# ALLPRINT-CAPBOARD-677512-POWER.net
KiCad netlist of a schematic drawn in Altium Designer
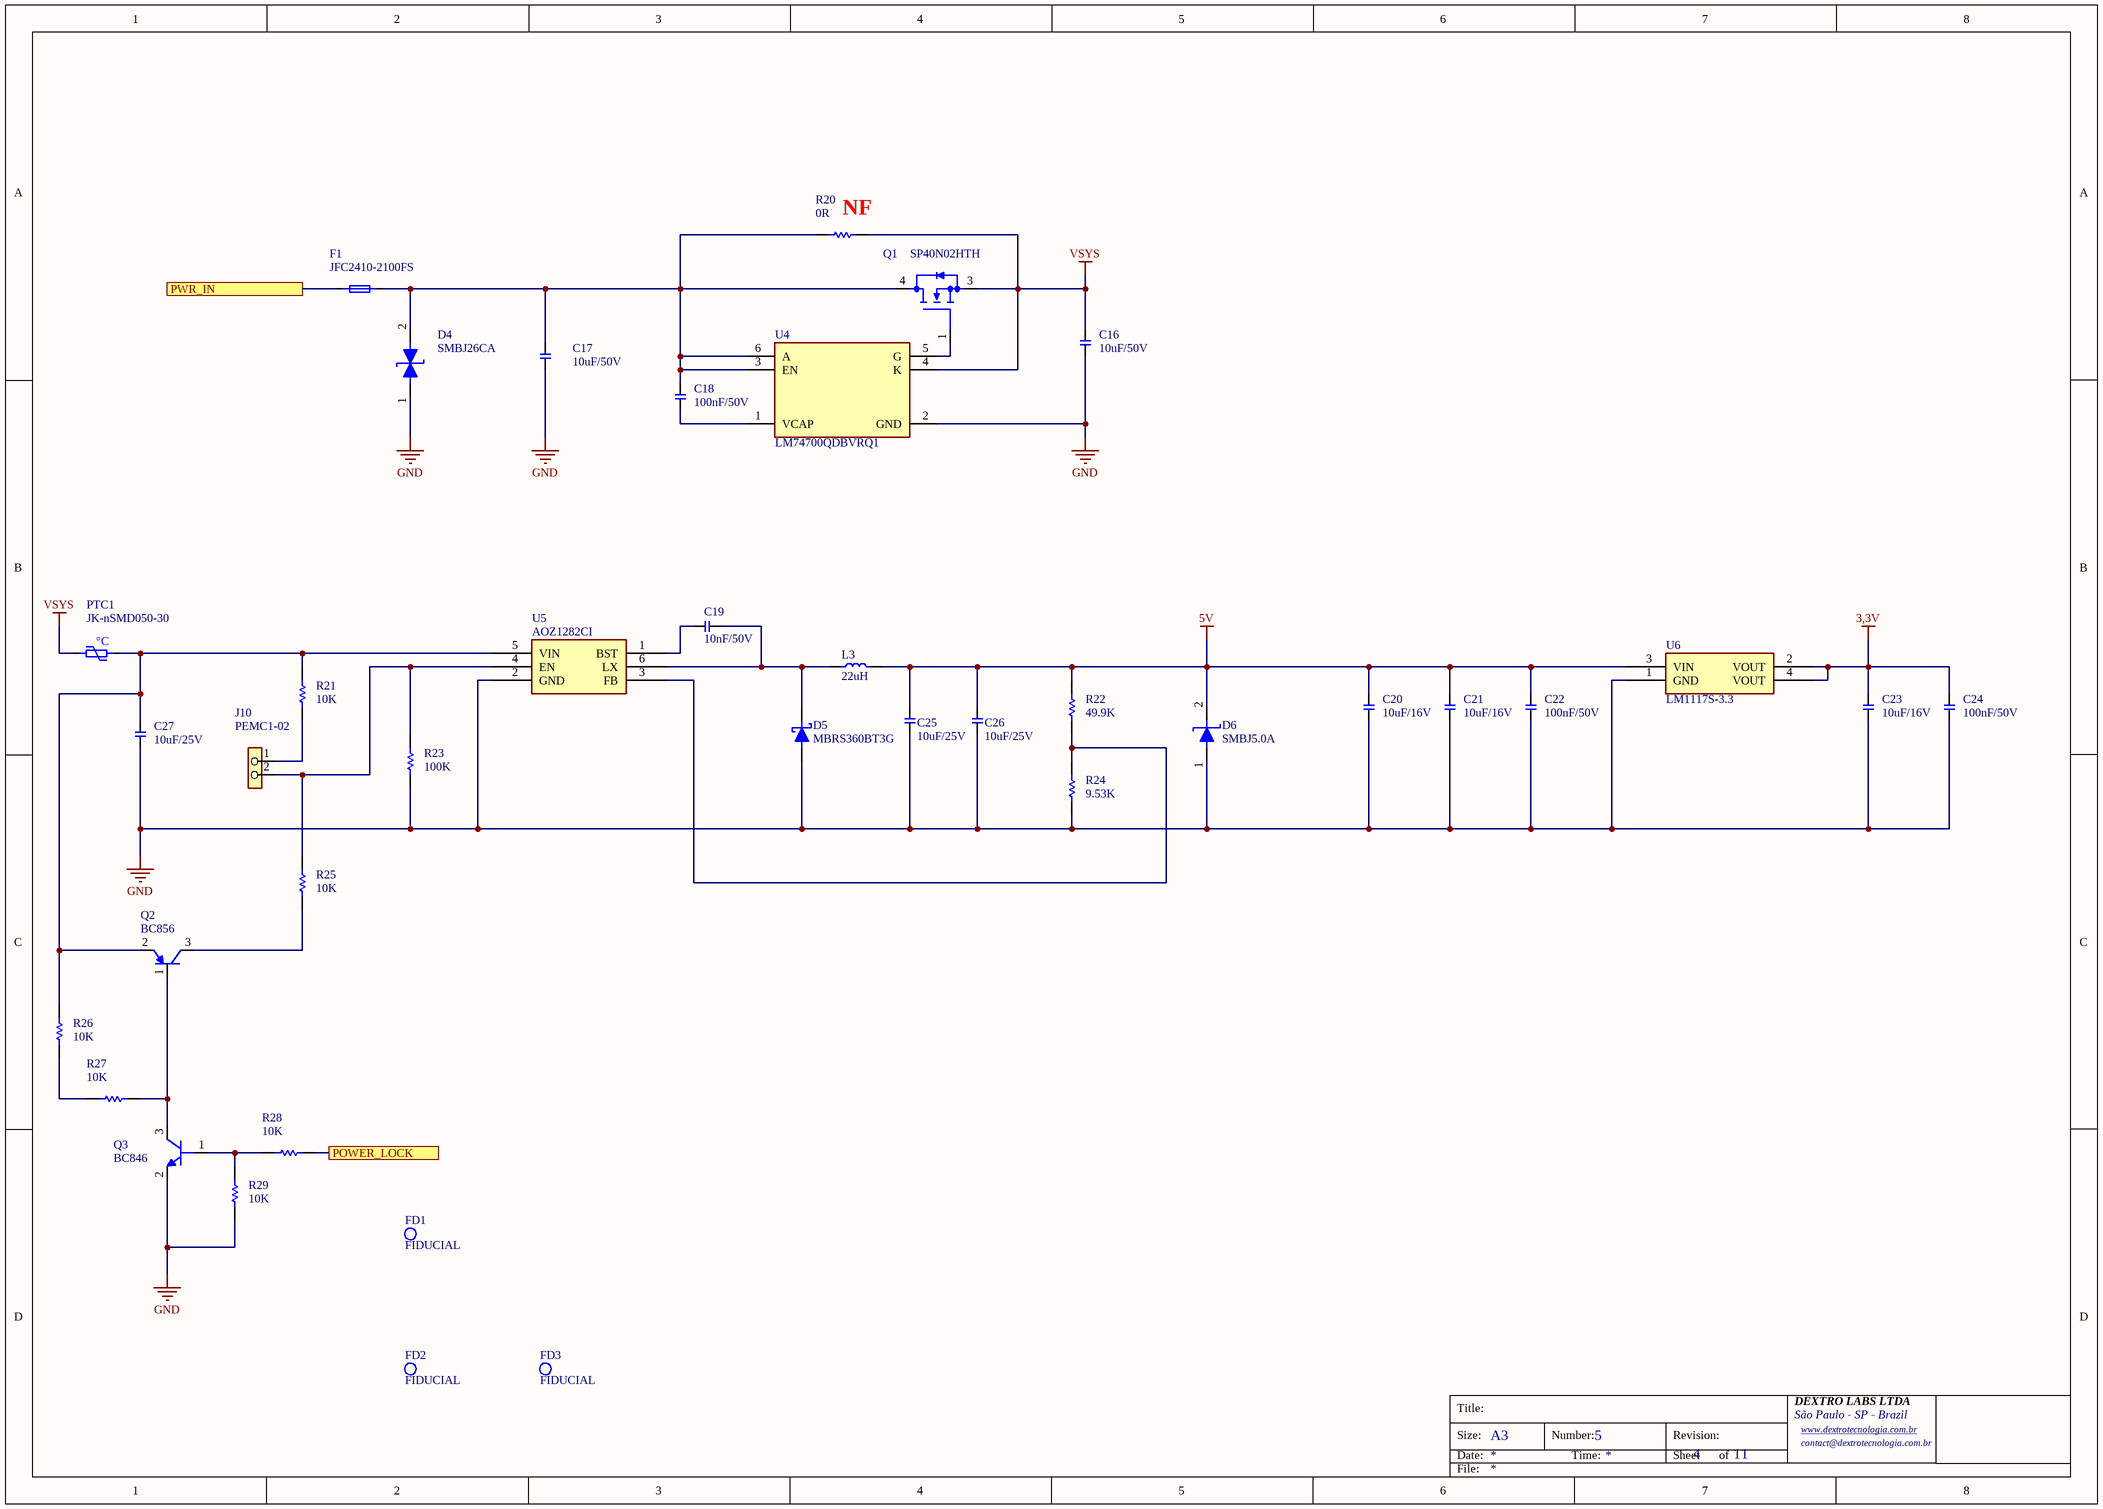
[diagram p0: ALLPRINT-CAPBOARD-677512-POWER.SchDoc]

(export (version "E")
  (design (tool "Eeschema 10.0.6"))
  (components
    (comp (ref "C16")
      (value "10uF/50V")
      (footprint "CAP-0805")
      (description "50V 10uF X5R ±10% 1206 Multilayer Ceramic Capacitors MLCC - SMD/SMT ROHS")
      (libsource (lib "dextro-labs") (part "CAP-10uF/50V-0805-X5R-MLCC"))
    )
    (comp (ref "C17")
      (value "10uF/50V")
      (footprint "CAP-0805")
      (description "50V 10uF X5R ±10% 1206 Multilayer Ceramic Capacitors MLCC - SMD/SMT ROHS")
      (libsource (lib "dextro-labs") (part "CAP-10uF/50V-0805-X5R-MLCC"))
    )
    (comp (ref "C18")
      (value "100nF/50V")
      (footprint "CAP-0603")
      (description "50V 100nF X7R ±10% 0603 Multilayer Ceramic Capacitors MLCC - SMD/SMT ROHS")
      (libsource (lib "dextro-labs") (part "CAP-100nF/50V-0603-X7R-MLCC"))
    )
    (comp (ref "C19")
      (value "10nF/50V")
      (footprint "CAP-0603")
      (description "50V 10nF X7R ±10% 0603 Multilayer Ceramic Capacitors MLCC - SMD/SMT ROHS")
      (libsource (lib "dextro-labs") (part "CAP-10nF/50V-0603-X7R-MLCC"))
    )
    (comp (ref "C20")
      (value "10uF/16V")
      (footprint "CAP-0603")
      (description "16V 10uF X5R ±20% 0603 Multilayer Ceramic Capacitors MLCC - SMD/SMT ROHS")
      (libsource (lib "dextro-labs") (part "CAP-10uF/16V-0603-X5R"))
    )
    (comp (ref "C21")
      (value "10uF/16V")
      (footprint "CAP-0603")
      (description "16V 10uF X5R ±20% 0603 Multilayer Ceramic Capacitors MLCC - SMD/SMT ROHS")
      (libsource (lib "dextro-labs") (part "CAP-10uF/16V-0603-X5R"))
    )
    (comp (ref "C22")
      (value "100nF/50V")
      (footprint "CAP-0603")
      (description "50V 100nF X7R ±10% 0603 Multilayer Ceramic Capacitors MLCC - SMD/SMT ROHS")
      (libsource (lib "dextro-labs") (part "CAP-100nF/50V-0603-X7R-MLCC"))
    )
    (comp (ref "C23")
      (value "10uF/16V")
      (footprint "CAP-0603")
      (description "16V 10uF X5R ±20% 0603 Multilayer Ceramic Capacitors MLCC - SMD/SMT ROHS")
      (libsource (lib "dextro-labs") (part "CAP-10uF/16V-0603-X5R"))
    )
    (comp (ref "C24")
      (value "100nF/50V")
      (footprint "CAP-0603")
      (description "50V 100nF X7R ±10% 0603 Multilayer Ceramic Capacitors MLCC - SMD/SMT ROHS")
      (libsource (lib "dextro-labs") (part "CAP-100nF/50V-0603-X7R-MLCC"))
    )
    (comp (ref "C25")
      (value "10uF/25V")
      (footprint "CAP-0805")
      (description "25V 10uF X5R ±10% 0805 Ceramic Capacitors ROHS")
      (libsource (lib "dextro-labs") (part "CAP-10uF/25V-0805-X5R-MLCC"))
    )
    (comp (ref "C26")
      (value "10uF/25V")
      (footprint "CAP-0805")
      (description "25V 10uF X5R ±10% 0805 Ceramic Capacitors ROHS")
      (libsource (lib "dextro-labs") (part "CAP-10uF/25V-0805-X5R-MLCC"))
    )
    (comp (ref "C27")
      (value "10uF/25V")
      (footprint "CAP-0805")
      (description "25V 10uF X5R ±10% 0805 Ceramic Capacitors ROHS")
      (libsource (lib "dextro-labs") (part "CAP-10uF/25V-0805-X5R-MLCC"))
    )
    (comp (ref "D4")
      (value "SMBJ26CA")
      (footprint "DO214-AA")
      (description "28.9V 26V 42.1V 14.2A 600W Bidirectional DO-214AA(SMB) TVS Diodes RoHS")
      (libsource (lib "dextro-labs") (part "SMBJ26CA"))
    )
    (comp (ref "D5")
      (value "MBRS360BT3G")
      (footprint "DO214-AA")
      (description "125A 60V 630mV@3A 3A SMB(DO-214AA) Single Diodes RoHS")
      (libsource (lib "dextro-labs") (part "DIODE-SCHOTTKY-60V-3A-MBRS360BT3G"))
    )
    (comp (ref "D6")
      (value "SMBJ5.0A")
      (footprint "DO214-AA")
      (description "65.3A 600W 9.2V 6.4V Unidirectional 5V DO-214AA TVS Diodes RoHS")
      (libsource (lib "dextro-labs") (part "SMBJ5.0A"))
    )
    (comp (ref "F1")
      (value "JFC2410-2100FS")
      (footprint "FUSE-2410")
      (description "125V Surface Mount Fuse 10A 2410 Fuses RoHS")
      (libsource (lib "dextro-labs") (part "FUSE-125V-10A-2410"))
    )
    (comp (ref "FD1")
      (value "FIDUCIAL")
      (footprint "FIDUCIAL")
      (libsource (lib "dextro-labs") (part "FIDUCIAL"))
    )
    (comp (ref "FD2")
      (value "FIDUCIAL")
      (footprint "FIDUCIAL")
      (libsource (lib "dextro-labs") (part "FIDUCIAL"))
    )
    (comp (ref "FD3")
      (value "FIDUCIAL")
      (footprint "FIDUCIAL")
      (libsource (lib "dextro-labs") (part "FIDUCIAL"))
    )
    (comp (ref "J10")
      (value "PEMC1-02")
      (footprint "PEMC1-02")
      (description "CONECTOR PASSO 2,5mm\r\n250VCA\r\n3A\r\n10mOHMS")
      (libsource (lib "dextro-labs") (part "PEMC1-02"))
    )
    (comp (ref "L3")
      (value "22uH")
      (footprint "INDUTOR-6672")
      (description "2.6A 22uH ±20% 110mΩ SMD,7.2x6.6mm Fixed Inductors RoHS")
      (libsource (lib "dextro-labs") (part "FIXED-INDUCTOR-SMD-22uH-7.2X6.6mm-2.6A-110mΩ"))
    )
    (comp (ref "PTC1")
      (value "JK-nSMD050-30")
      (footprint "PTC-1206")
      (description "30V 500mA 100A 1A 150mΩ 1206 PTC Resettable Fuses ROHS")
      (libsource (lib "dextro-labs") (part "PTC-FUSE-30V-500mA-1206"))
    )
    (comp (ref "Q1")
      (value "SP40N02HTH")
      (footprint "TO-252-2")
      (description "40V 130A 2.5mΩ@10V 125W TO-252 Single FETs, MOSFETs RoHS")
      (libsource (lib "dextro-labs") (part "TRAN-MOSFET-N-CHAN-40V-130A-DPAK"))
    )
    (comp (ref "Q2")
      (value "BC856")
      (footprint "SOT23-3")
      (description "65V 220@2mA,5V 250mW 100mA PNP SOT-23 Bipolar (BJT) ROHS")
      (libsource (lib "dextro-labs") (part "TRANSISTOR-BC856B,215"))
    )
    (comp (ref "Q3")
      (value "BC846")
      (footprint "SOT23-3")
      (description "65V 200@10mA,5V 250mW 100mA NPN SOT-23 Bipolar (BJT) ROHS")
      (libsource (lib "dextro-labs") (part "TRANSISTOR-BC846B,215-SOT23"))
    )
    (comp (ref "R20")
      (value "0R")
      (footprint "RES-1206")
      (description "0Ω 250mW 200V Thick Film Resistor ±1% 1206 Chip Resistor - Surface Mount RoHS")
      (libsource (lib "dextro-labs") (part "RES-0R-1%-250mW-1206"))
    )
    (comp (ref "R21")
      (value "10K")
      (footprint "RES-0603")
      (description "100mW Thick Film Resistor 75V ±100ppm/℃ ±1% 10kΩ 0603 Chip Resistor - Surface Mount ROHS")
      (libsource (lib "dextro-labs") (part "RES-10K-1%-100mW-0603"))
    )
    (comp (ref "R22")
      (value "49.9K")
      (footprint "RES-0603")
      (description "100mW 49.9kΩ 75V ±100ppm/℃ Thick Film Resistor ±1% 0603 Chip Resistor - Surface Mount ROHS")
      (libsource (lib "dextro-labs") (part "RES-49.9K-1%-100mW-0603"))
    )
    (comp (ref "R23")
      (value "100K")
      (footprint "RES-0603")
      (description "100mW Thick Film Resistor 75V ±100ppm/℃ ±1% 100kΩ 0603 Chip Resistor - Surface Mount ROHS")
      (libsource (lib "dextro-labs") (part "RES-100K-1%-100mW-0603"))
    )
    (comp (ref "R24")
      (value "9.53K")
      (footprint "RES-0603")
      (description "100mW 9.53kΩ 75V ±100ppm/℃ Thick Film Resistor ±1% 0603 Chip Resistor - Surface Mount ROHS")
      (libsource (lib "dextro-labs") (part "RES-9.53K-1%-100mW-0603"))
    )
    (comp (ref "R25")
      (value "10K")
      (footprint "RES-0603")
      (description "100mW Thick Film Resistor 75V ±100ppm/℃ ±1% 10kΩ 0603 Chip Resistor - Surface Mount ROHS")
      (libsource (lib "dextro-labs") (part "RES-10K-1%-100mW-0603"))
    )
    (comp (ref "R26")
      (value "10K")
      (footprint "RES-0603")
      (description "100mW Thick Film Resistor 75V ±100ppm/℃ ±1% 10kΩ 0603 Chip Resistor - Surface Mount ROHS")
      (libsource (lib "dextro-labs") (part "RES-10K-1%-100mW-0603"))
    )
    (comp (ref "R27")
      (value "10K")
      (footprint "RES-0603")
      (description "100mW Thick Film Resistor 75V ±100ppm/℃ ±1% 10kΩ 0603 Chip Resistor - Surface Mount ROHS")
      (libsource (lib "dextro-labs") (part "RES-10K-1%-100mW-0603"))
    )
    (comp (ref "R28")
      (value "10K")
      (footprint "RES-0603")
      (description "100mW Thick Film Resistor 75V ±100ppm/℃ ±1% 10kΩ 0603 Chip Resistor - Surface Mount ROHS")
      (libsource (lib "dextro-labs") (part "RES-10K-1%-100mW-0603"))
    )
    (comp (ref "R29")
      (value "10K")
      (footprint "RES-0603")
      (description "100mW Thick Film Resistor 75V ±100ppm/℃ ±1% 10kΩ 0603 Chip Resistor - Surface Mount ROHS")
      (libsource (lib "dextro-labs") (part "RES-10K-1%-100mW-0603"))
    )
    (comp (ref "U4")
      (value "LM74700QDBVRQ1")
      (footprint "SOT23-6")
      (description "Low IQ Battery Reverse Protection Ideal Diode Controller")
      (libsource (lib "dextro-labs") (part "IC-OR-CONTROLLER-LM74700QDBVRQ1"))
    )
    (comp (ref "U5")
      (value "AOZ1282CI")
      (footprint "SOT23-6")
      (description "Step-down type Adjustable 800mV~36V 1.2A 4.5V~36V SOT-23-6 DC-DC Converters ROHS")
      (libsource (lib "dextro-sch") (part "AOZ1282CI"))
    )
    (comp (ref "U6")
      (value "LM1117S-3.3")
      (footprint "SOT223")
      (libsource (lib "dextro-labs") (part "LM1117S-3.3"))
    )
  )
  (nets
    (net (code "1") (name "/POWER_LOCK") (class "Default")
      (node (ref "R28") (pin "1") (pinfunction "1_1") (pintype "passive"))
    )
    (net (code "2") (name "/PWR_IN") (class "Default")
      (node (ref "F1") (pin "1") (pinfunction "1_1") (pintype "passive"))
    )
    (net (code "3") (name "3,3V") (class "Default")
      (node (ref "C23") (pin "2") (pinfunction "2_2") (pintype "passive"))
      (node (ref "C24") (pin "2") (pinfunction "2_2") (pintype "passive"))
      (node (ref "U6") (pin "2") (pinfunction "VOUT_2") (pintype "passive"))
      (node (ref "U6") (pin "4") (pinfunction "VOUT_4") (pintype "passive"))
    )
    (net (code "4") (name "5V") (class "Default")
      (node (ref "C20") (pin "2") (pinfunction "2_2") (pintype "passive"))
      (node (ref "C21") (pin "2") (pinfunction "2_2") (pintype "passive"))
      (node (ref "C22") (pin "2") (pinfunction "2_2") (pintype "passive"))
      (node (ref "C25") (pin "2") (pinfunction "2_2") (pintype "passive"))
      (node (ref "C26") (pin "2") (pinfunction "2_2") (pintype "passive"))
      (node (ref "D6") (pin "2") (pinfunction "K_2") (pintype "passive"))
      (node (ref "L3") (pin "2") (pinfunction "2_2") (pintype "passive"))
      (node (ref "R22") (pin "2") (pinfunction "2_2") (pintype "passive"))
      (node (ref "U6") (pin "3") (pinfunction "VIN_3") (pintype "passive"))
    )
    (net (code "5") (name "GND") (class "Default")
      (node (ref "C16") (pin "1") (pinfunction "1_1") (pintype "passive"))
      (node (ref "C17") (pin "1") (pinfunction "1_1") (pintype "passive"))
      (node (ref "C20") (pin "1") (pinfunction "1_1") (pintype "passive"))
      (node (ref "C21") (pin "1") (pinfunction "1_1") (pintype "passive"))
      (node (ref "C22") (pin "1") (pinfunction "1_1") (pintype "passive"))
      (node (ref "C23") (pin "1") (pinfunction "1_1") (pintype "passive"))
      (node (ref "C24") (pin "1") (pinfunction "1_1") (pintype "passive"))
      (node (ref "C25") (pin "1") (pinfunction "1_1") (pintype "passive"))
      (node (ref "C26") (pin "1") (pinfunction "1_1") (pintype "passive"))
      (node (ref "C27") (pin "1") (pinfunction "1_1") (pintype "passive"))
      (node (ref "D4") (pin "1") (pinfunction "A1_1") (pintype "passive"))
      (node (ref "D5") (pin "1") (pinfunction "A_1") (pintype "passive"))
      (node (ref "D6") (pin "1") (pinfunction "A_1") (pintype "passive"))
      (node (ref "Q3") (pin "2") (pinfunction "2_2") (pintype "passive"))
      (node (ref "R23") (pin "1") (pinfunction "1_1") (pintype "passive"))
      (node (ref "R24") (pin "1") (pinfunction "1_1") (pintype "passive"))
      (node (ref "R29") (pin "2") (pinfunction "2_2") (pintype "passive"))
      (node (ref "U4") (pin "2") (pinfunction "GND_2") (pintype "passive"))
      (node (ref "U5") (pin "2") (pinfunction "GND_2") (pintype "passive"))
      (node (ref "U6") (pin "1") (pinfunction "GND_1") (pintype "passive"))
    )
    (net (code "6") (name "Net-(D4-A2)") (class "Default")
      (node (ref "C17") (pin "2") (pinfunction "2_2") (pintype "passive"))
      (node (ref "C18") (pin "2") (pinfunction "2_2") (pintype "passive"))
      (node (ref "D4") (pin "2") (pinfunction "A2_2") (pintype "passive"))
      (node (ref "F1") (pin "2") (pinfunction "2_2") (pintype "passive"))
      (node (ref "Q1") (pin "4") (pinfunction "D_4") (pintype "passive"))
      (node (ref "R20") (pin "1") (pinfunction "1_1") (pintype "passive"))
      (node (ref "U4") (pin "3") (pinfunction "EN_3") (pintype "passive"))
      (node (ref "U4") (pin "6") (pinfunction "A_6") (pintype "passive"))
    )
    (net (code "7") (name "Net-(D5-K)") (class "Default")
      (node (ref "C19") (pin "1") (pinfunction "1_1") (pintype "passive"))
      (node (ref "D5") (pin "2") (pinfunction "K_2") (pintype "passive"))
      (node (ref "L3") (pin "1") (pinfunction "1_1") (pintype "passive"))
      (node (ref "U5") (pin "6") (pinfunction "LX_6") (pintype "passive"))
    )
    (net (code "8") (name "Net-(J10-Pad1)") (class "Default")
      (node (ref "J10") (pin "1") (pinfunction "1_1") (pintype "passive"))
      (node (ref "R21") (pin "2") (pinfunction "2_2") (pintype "passive"))
    )
    (net (code "9") (name "Net-(Q1-G])") (class "Default")
      (node (ref "Q1") (pin "1") (pinfunction "G]_1") (pintype "passive"))
      (node (ref "U4") (pin "5") (pinfunction "G_5") (pintype "passive"))
    )
    (net (code "10") (name "Net-(Q2-B)") (class "Default")
      (node (ref "Q2") (pin "1") (pinfunction "B_1") (pintype "passive"))
      (node (ref "Q3") (pin "3") (pinfunction "3_3") (pintype "passive"))
      (node (ref "R27") (pin "1") (pinfunction "1_1") (pintype "passive"))
    )
    (net (code "11") (name "Net-(Q2-C)") (class "Default")
      (node (ref "Q2") (pin "3") (pinfunction "C_3") (pintype "passive"))
      (node (ref "R25") (pin "2") (pinfunction "2_2") (pintype "passive"))
    )
    (net (code "12") (name "Net-(Q2-E)") (class "Default")
      (node (ref "C27") (pin "2") (pinfunction "2_2") (pintype "passive"))
      (node (ref "PTC1") (pin "2") (pinfunction "2_2") (pintype "passive"))
      (node (ref "Q2") (pin "2") (pinfunction "E_2") (pintype "passive"))
      (node (ref "R21") (pin "1") (pinfunction "1_1") (pintype "passive"))
      (node (ref "R26") (pin "2") (pinfunction "2_2") (pintype "passive"))
      (node (ref "U5") (pin "5") (pinfunction "VIN_5") (pintype "passive"))
    )
    (net (code "13") (name "Net-(Q3-Pad1)") (class "Default")
      (node (ref "Q3") (pin "1") (pinfunction "1_1") (pintype "passive"))
      (node (ref "R28") (pin "2") (pinfunction "2_2") (pintype "passive"))
      (node (ref "R29") (pin "1") (pinfunction "1_1") (pintype "passive"))
    )
    (net (code "14") (name "Net-(R26-Pad1)") (class "Default")
      (node (ref "R26") (pin "1") (pinfunction "1_1") (pintype "passive"))
      (node (ref "R27") (pin "2") (pinfunction "2_2") (pintype "passive"))
    )
    (net (code "15") (name "Net-(U4-VCAP)") (class "Default")
      (node (ref "C18") (pin "1") (pinfunction "1_1") (pintype "passive"))
      (node (ref "U4") (pin "1") (pinfunction "VCAP_1") (pintype "passive"))
    )
    (net (code "16") (name "Net-(U5-BST)") (class "Default")
      (node (ref "C19") (pin "2") (pinfunction "2_2") (pintype "passive"))
      (node (ref "U5") (pin "1") (pinfunction "BST_1") (pintype "passive"))
    )
    (net (code "17") (name "Net-(U5-EN)") (class "Default")
      (node (ref "J10") (pin "2") (pinfunction "2_2") (pintype "passive"))
      (node (ref "R23") (pin "2") (pinfunction "2_2") (pintype "passive"))
      (node (ref "R25") (pin "1") (pinfunction "1_1") (pintype "passive"))
      (node (ref "U5") (pin "4") (pinfunction "EN_4") (pintype "passive"))
    )
    (net (code "18") (name "Net-(U5-FB)") (class "Default")
      (node (ref "R22") (pin "1") (pinfunction "1_1") (pintype "passive"))
      (node (ref "R24") (pin "2") (pinfunction "2_2") (pintype "passive"))
      (node (ref "U5") (pin "3") (pinfunction "FB_3") (pintype "passive"))
    )
    (net (code "19") (name "VSYS") (class "Default")
      (node (ref "C16") (pin "2") (pinfunction "2_2") (pintype "passive"))
      (node (ref "PTC1") (pin "1") (pinfunction "1_1") (pintype "passive"))
      (node (ref "Q1") (pin "3") (pinfunction "S_3") (pintype "passive"))
      (node (ref "R20") (pin "2") (pinfunction "2_2") (pintype "passive"))
      (node (ref "U4") (pin "4") (pinfunction "K_4") (pintype "passive"))
    )
  )
)
